# Output_Stage.net
KiCad netlist of a schematic drawn in Altium Designer
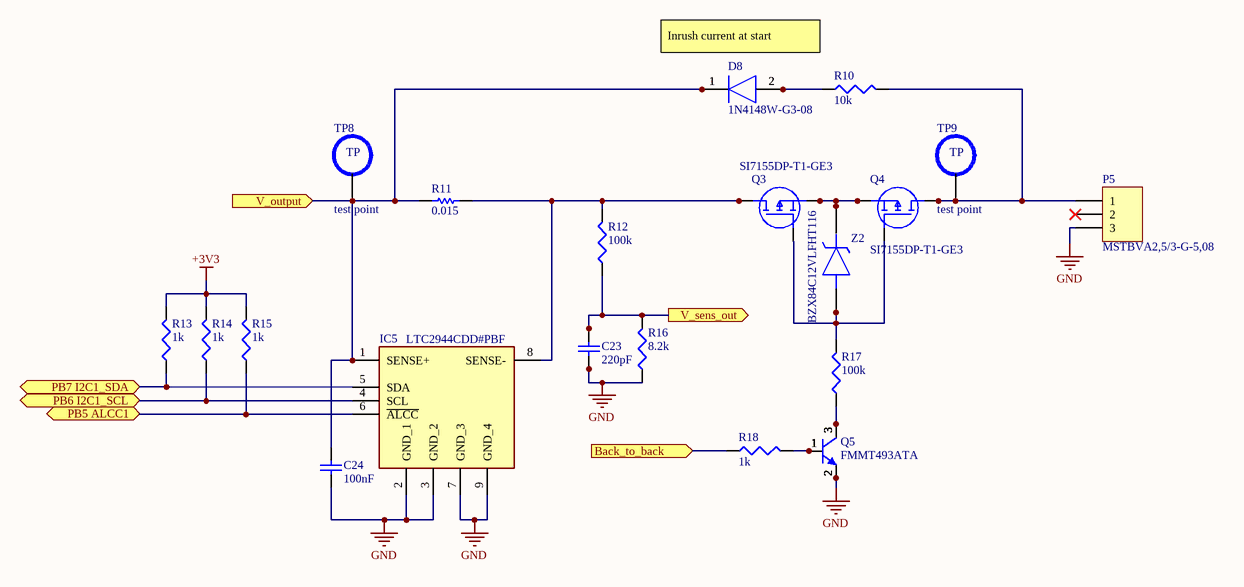
[diagram p0: Output_Stage.SchDoc]

(export (version "E")
  (design (tool "Eeschema 10.0.6"))
  (components
    (comp (ref "C23")
      (value "220pF")
      (footprint "PcbLib1:CAPC3216X180N")
      (description "Capacitor 220pF")
      (fields (field (name "PUBLISHER") "Altium Limited"))
      (libsource (lib "Sch_Capacitors") (part "VJ1206A221JXBCW1BC"))
    )
    (comp (ref "C24")
      (value "100nF")
      (footprint "CAPC3216X180N")
      (description "Capacitor 100nF")
      (fields (field (name "Comment") "CC1206KKX7R0BB104") (field (name "PUBLISHER") "Altium Limited"))
      (libsource (lib "Sch_Capacitors") (part "CC1206KKX7R0BB104"))
    )
    (comp (ref "D8")
      (value "1N4148W-G3-08")
      (footprint "SOD3716X135N")
      (description "Diode")
      (fields (field (name "MOUSER PART NUMBER") "78-1N4148W-G3-08"))
      (libsource (lib "Sch_Diodes") (part "1N4148W-G3-08"))
    )
    (comp (ref "IC5")
      (value "LTC2944CDD#PBF")
      (footprint "SON50P300X300X80-9N-D")
      (description "Integrated Circuit")
      (fields (field (name "MOUSER PART NUMBER") "584-LTC2944CDDPBF"))
      (libsource (lib "Sch_IC") (part "LTC2944CDD#PBF"))
    )
    (comp (ref "P5")
      (value "MSTBVA2,5/3-G-5,08")
      (footprint "HDR1X3")
      (description "Header, 3-Pin")
      (fields (field (name "PUBLISHER") "Altium Limited"))
      (libsource (lib "Sch_Headers") (part "MSTBVA2,5/3-G-5,08"))
    )
    (comp (ref "Q3")
      (value "SI7155DP-T1-GE3")
      (footprint "SI7141DPT1GE3")
      (description "MOSFET (P-Channel)")
      (libsource (lib "Sch_Transistors") (part "SI7155DP-T1-GE3"))
    )
    (comp (ref "Q4")
      (value "SI7155DP-T1-GE3")
      (footprint "SI7141DPT1GE3")
      (description "MOSFET (P-Channel)")
      (libsource (lib "Sch_Transistors") (part "SI7155DP-T1-GE3"))
    )
    (comp (ref "Q5")
      (value "FMMT493ATA")
      (footprint "SOT95P230X110-3N")
      (description "Transistor BJT PNP")
      (fields (field (name "MOUSER PART NUMBER") "522-FMMT493ATA"))
      (libsource (lib "Sch_Transistors") (part "FMMT493ATA"))
    )
    (comp (ref "R10")
      (value "10k")
      (footprint "RESC3216X75N")
      (description "Resistor 10k")
      (fields (field (name "Comment") "MCWR12X1002FTL") (field (name "PUBLISHER") "Altium Limited"))
      (libsource (lib "Sch_Resistors") (part "MCWR12X1002FTL"))
    )
    (comp (ref "R11")
      (value "0.015")
      (footprint "RESC3216X75N")
      (description "Shunt resistor 0.015")
      (fields (field (name "Comment") "ERJ8BWFR015V") (field (name "PUBLISHER") "Altium Limited"))
      (libsource (lib "Sch_Resistors") (part "ERJ8BWFR015V"))
    )
    (comp (ref "R12")
      (value "100k")
      (footprint "RESC3216X75N")
      (description "Resistor 100k")
      (fields (field (name "Comment") "100KΩ") (field (name "PUBLISHER") "Altium Limited"))
      (libsource (lib "Sch_Resistors") (part "MCWR12X1003FTL"))
    )
    (comp (ref "R13")
      (value "1k")
      (footprint "RESC3216X75N")
      (description "Resistor 1k")
      (fields (field (name "Comment") "MCHP06W2F1001T5E") (field (name "PUBLISHER") "Altium Limited"))
      (libsource (lib "Sch_Resistors") (part "MCHP06W2F1001T5E"))
    )
    (comp (ref "R14")
      (value "1k")
      (footprint "RESC3216X75N")
      (description "Resistor 1k")
      (fields (field (name "Comment") "MCHP06W2F1001T5E") (field (name "PUBLISHER") "Altium Limited"))
      (libsource (lib "Sch_Resistors") (part "MCHP06W2F1001T5E"))
    )
    (comp (ref "R15")
      (value "1k")
      (footprint "RESC3216X75N")
      (description "Resistor 1k")
      (fields (field (name "Comment") "MCHP06W2F1001T5E") (field (name "PUBLISHER") "Altium Limited"))
      (libsource (lib "Sch_Resistors") (part "MCHP06W2F1001T5E"))
    )
    (comp (ref "R16")
      (value "8.2k")
      (footprint "RESC3216X75N")
      (description "Resistor 8.2k")
      (fields (field (name "Comment") "8.2KΩ") (field (name "PUBLISHER") "Altium Limited"))
      (libsource (lib "Sch_Resistors") (part "CRGCQ1206F8K2"))
    )
    (comp (ref "R17")
      (value "100k")
      (footprint "RESC3216X75N")
      (description "Resistor 100k")
      (fields (field (name "Comment") "MCWR12X1003FTL") (field (name "PUBLISHER") "Altium Limited"))
      (libsource (lib "Sch_Resistors") (part "MCWR12X1003FTL"))
    )
    (comp (ref "R18")
      (value "1k")
      (footprint "RESC3216X75N")
      (description "Resistor 1k")
      (fields (field (name "Comment") "MCHP06W2F1001T5E") (field (name "PUBLISHER") "Altium Limited"))
      (libsource (lib "Sch_Resistors") (part "MCHP06W2F1001T5E"))
    )
    (comp (ref "TP8")
      (value "test point")
      (footprint "Test point")
      (libsource (lib "Sch_Headers") (part "test point"))
    )
    (comp (ref "TP9")
      (value "test point")
      (footprint "Test point")
      (libsource (lib "Sch_Headers") (part "test point"))
    )
    (comp (ref "Z2")
      (value "BZX84C12VLFHT116")
      (footprint "SOT95P240X115-3N")
      (description "Zener Diode")
      (libsource (lib "Sch_Diodes") (part "BZX84C12VLFHT116"))
    )
  )
  (nets
    (net (code "1") (name "+3V3") (class "Default")
      (node (ref "R13") (pin "2") (pinfunction "2_2") (pintype "passive"))
      (node (ref "R14") (pin "2") (pinfunction "2_2") (pintype "passive"))
      (node (ref "R15") (pin "2") (pinfunction "2_2") (pintype "passive"))
    )
    (net (code "2") (name "/Back_to_back") (class "Default")
      (node (ref "R18") (pin "1") (pinfunction "1_1") (pintype "passive"))
    )
    (net (code "3") (name "/PB5 ALCC1") (class "Default")
      (node (ref "IC5") (pin "6") (pinfunction "~{ALCC}_6") (pintype "passive"))
      (node (ref "R15") (pin "1") (pinfunction "1_1") (pintype "passive"))
    )
    (net (code "4") (name "/PB6 I2C1_SCL") (class "Default")
      (node (ref "IC5") (pin "4") (pinfunction "SCL_4") (pintype "passive"))
      (node (ref "R14") (pin "1") (pinfunction "1_1") (pintype "passive"))
    )
    (net (code "5") (name "/PB7 I2C1_SDA") (class "Default")
      (node (ref "IC5") (pin "5") (pinfunction "SDA_5") (pintype "passive"))
      (node (ref "R13") (pin "1") (pinfunction "1_1") (pintype "passive"))
    )
    (net (code "6") (name "/V_output") (class "Default")
      (node (ref "C24") (pin "2") (pinfunction "2_2") (pintype "passive"))
      (node (ref "D8") (pin "1") (pinfunction "K_1") (pintype "passive"))
      (node (ref "IC5") (pin "1") (pinfunction "SENSE+_1") (pintype "passive"))
      (node (ref "R11") (pin "1") (pinfunction "1_1") (pintype "passive"))
      (node (ref "TP8") (pin "5") (pinfunction "5_5") (pintype "passive"))
    )
    (net (code "7") (name "/V_sens_out") (class "Default")
      (node (ref "C23") (pin "2") (pinfunction "2_2") (pintype "passive"))
      (node (ref "R12") (pin "1") (pinfunction "1_1") (pintype "passive"))
      (node (ref "R16") (pin "2") (pinfunction "2_2") (pintype "passive"))
    )
    (net (code "8") (name "GND") (class "Default")
      (node (ref "C23") (pin "1") (pinfunction "1_1") (pintype "passive"))
      (node (ref "C24") (pin "1") (pinfunction "1_1") (pintype "passive"))
      (node (ref "IC5") (pin "2") (pinfunction "GND_1_2") (pintype "passive"))
      (node (ref "IC5") (pin "3") (pinfunction "GND_2_3") (pintype "passive"))
      (node (ref "IC5") (pin "7") (pinfunction "GND_3_7") (pintype "passive"))
      (node (ref "IC5") (pin "9") (pinfunction "GND_4_9") (pintype "passive"))
      (node (ref "P5") (pin "3") (pinfunction "3_3") (pintype "passive"))
      (node (ref "Q5") (pin "2") (pinfunction "E_2") (pintype "passive"))
      (node (ref "R16") (pin "1") (pinfunction "1_1") (pintype "passive"))
    )
    (net (code "9") (name "Net-(D8-A)") (class "Default")
      (node (ref "D8") (pin "2") (pinfunction "A_2") (pintype "passive"))
      (node (ref "R10") (pin "1") (pinfunction "1_1") (pintype "passive"))
    )
    (net (code "10") (name "Net-(IC5-SENSE-)") (class "Default")
      (node (ref "IC5") (pin "8") (pinfunction "SENSE-_8") (pintype "passive"))
      (node (ref "Q3") (pin "5") (pinfunction "D_5") (pintype "passive"))
      (node (ref "Q3") (pin "6") (pinfunction "D_6") (pintype "passive"))
      (node (ref "Q3") (pin "7") (pinfunction "D_7") (pintype "passive"))
      (node (ref "Q3") (pin "8") (pinfunction "D_8") (pintype "passive"))
      (node (ref "R11") (pin "2") (pinfunction "2_2") (pintype "passive"))
      (node (ref "R12") (pin "2") (pinfunction "2_2") (pintype "passive"))
    )
    (net (code "11") (name "Net-(P5-Pad1)") (class "Default")
      (node (ref "P5") (pin "1") (pinfunction "1_1") (pintype "passive"))
      (node (ref "Q4") (pin "5") (pinfunction "D_5") (pintype "passive"))
      (node (ref "Q4") (pin "6") (pinfunction "D_6") (pintype "passive"))
      (node (ref "Q4") (pin "7") (pinfunction "D_7") (pintype "passive"))
      (node (ref "Q4") (pin "8") (pinfunction "D_8") (pintype "passive"))
      (node (ref "R10") (pin "2") (pinfunction "2_2") (pintype "passive"))
      (node (ref "TP9") (pin "5") (pinfunction "5_5") (pintype "passive"))
    )
    (net (code "12") (name "Net-(Q3-G)") (class "Default")
      (node (ref "Q3") (pin "1") (pinfunction "G_1") (pintype "passive"))
      (node (ref "Q4") (pin "1") (pinfunction "G_1") (pintype "passive"))
      (node (ref "R17") (pin "2") (pinfunction "2_2") (pintype "passive"))
      (node (ref "Z2") (pin "1") (pinfunction "A_1") (pintype "passive"))
      (node (ref "Z2") (pin "2") (pinfunction "A_2") (pintype "passive"))
    )
    (net (code "13") (name "Net-(Q5-B)") (class "Default")
      (node (ref "Q5") (pin "1") (pinfunction "B_1") (pintype "passive"))
      (node (ref "R18") (pin "2") (pinfunction "2_2") (pintype "passive"))
    )
    (net (code "14") (name "Net-(Q5-C)") (class "Default")
      (node (ref "Q5") (pin "3") (pinfunction "C_3") (pintype "passive"))
      (node (ref "R17") (pin "1") (pinfunction "1_1") (pintype "passive"))
    )
    (net (code "15") (name "Net-(Z2-K)") (class "Default")
      (node (ref "Q3") (pin "2") (pinfunction "S_2") (pintype "passive"))
      (node (ref "Q3") (pin "3") (pinfunction "S_3") (pintype "passive"))
      (node (ref "Q3") (pin "4") (pinfunction "S_4") (pintype "passive"))
      (node (ref "Q4") (pin "2") (pinfunction "S_2") (pintype "passive"))
      (node (ref "Q4") (pin "3") (pinfunction "S_3") (pintype "passive"))
      (node (ref "Q4") (pin "4") (pinfunction "S_4") (pintype "passive"))
      (node (ref "Z2") (pin "3") (pinfunction "K_3") (pintype "passive"))
    )
    (net (code "16") (name "unconnected-(P5-Pad2)") (class "Default")
      (node (ref "P5") (pin "2") (pinfunction "2_2") (pintype "passive+no_connect"))
    )
  )
)
